# Vibration.net
KiCad netlist of a schematic drawn in Altium Designer
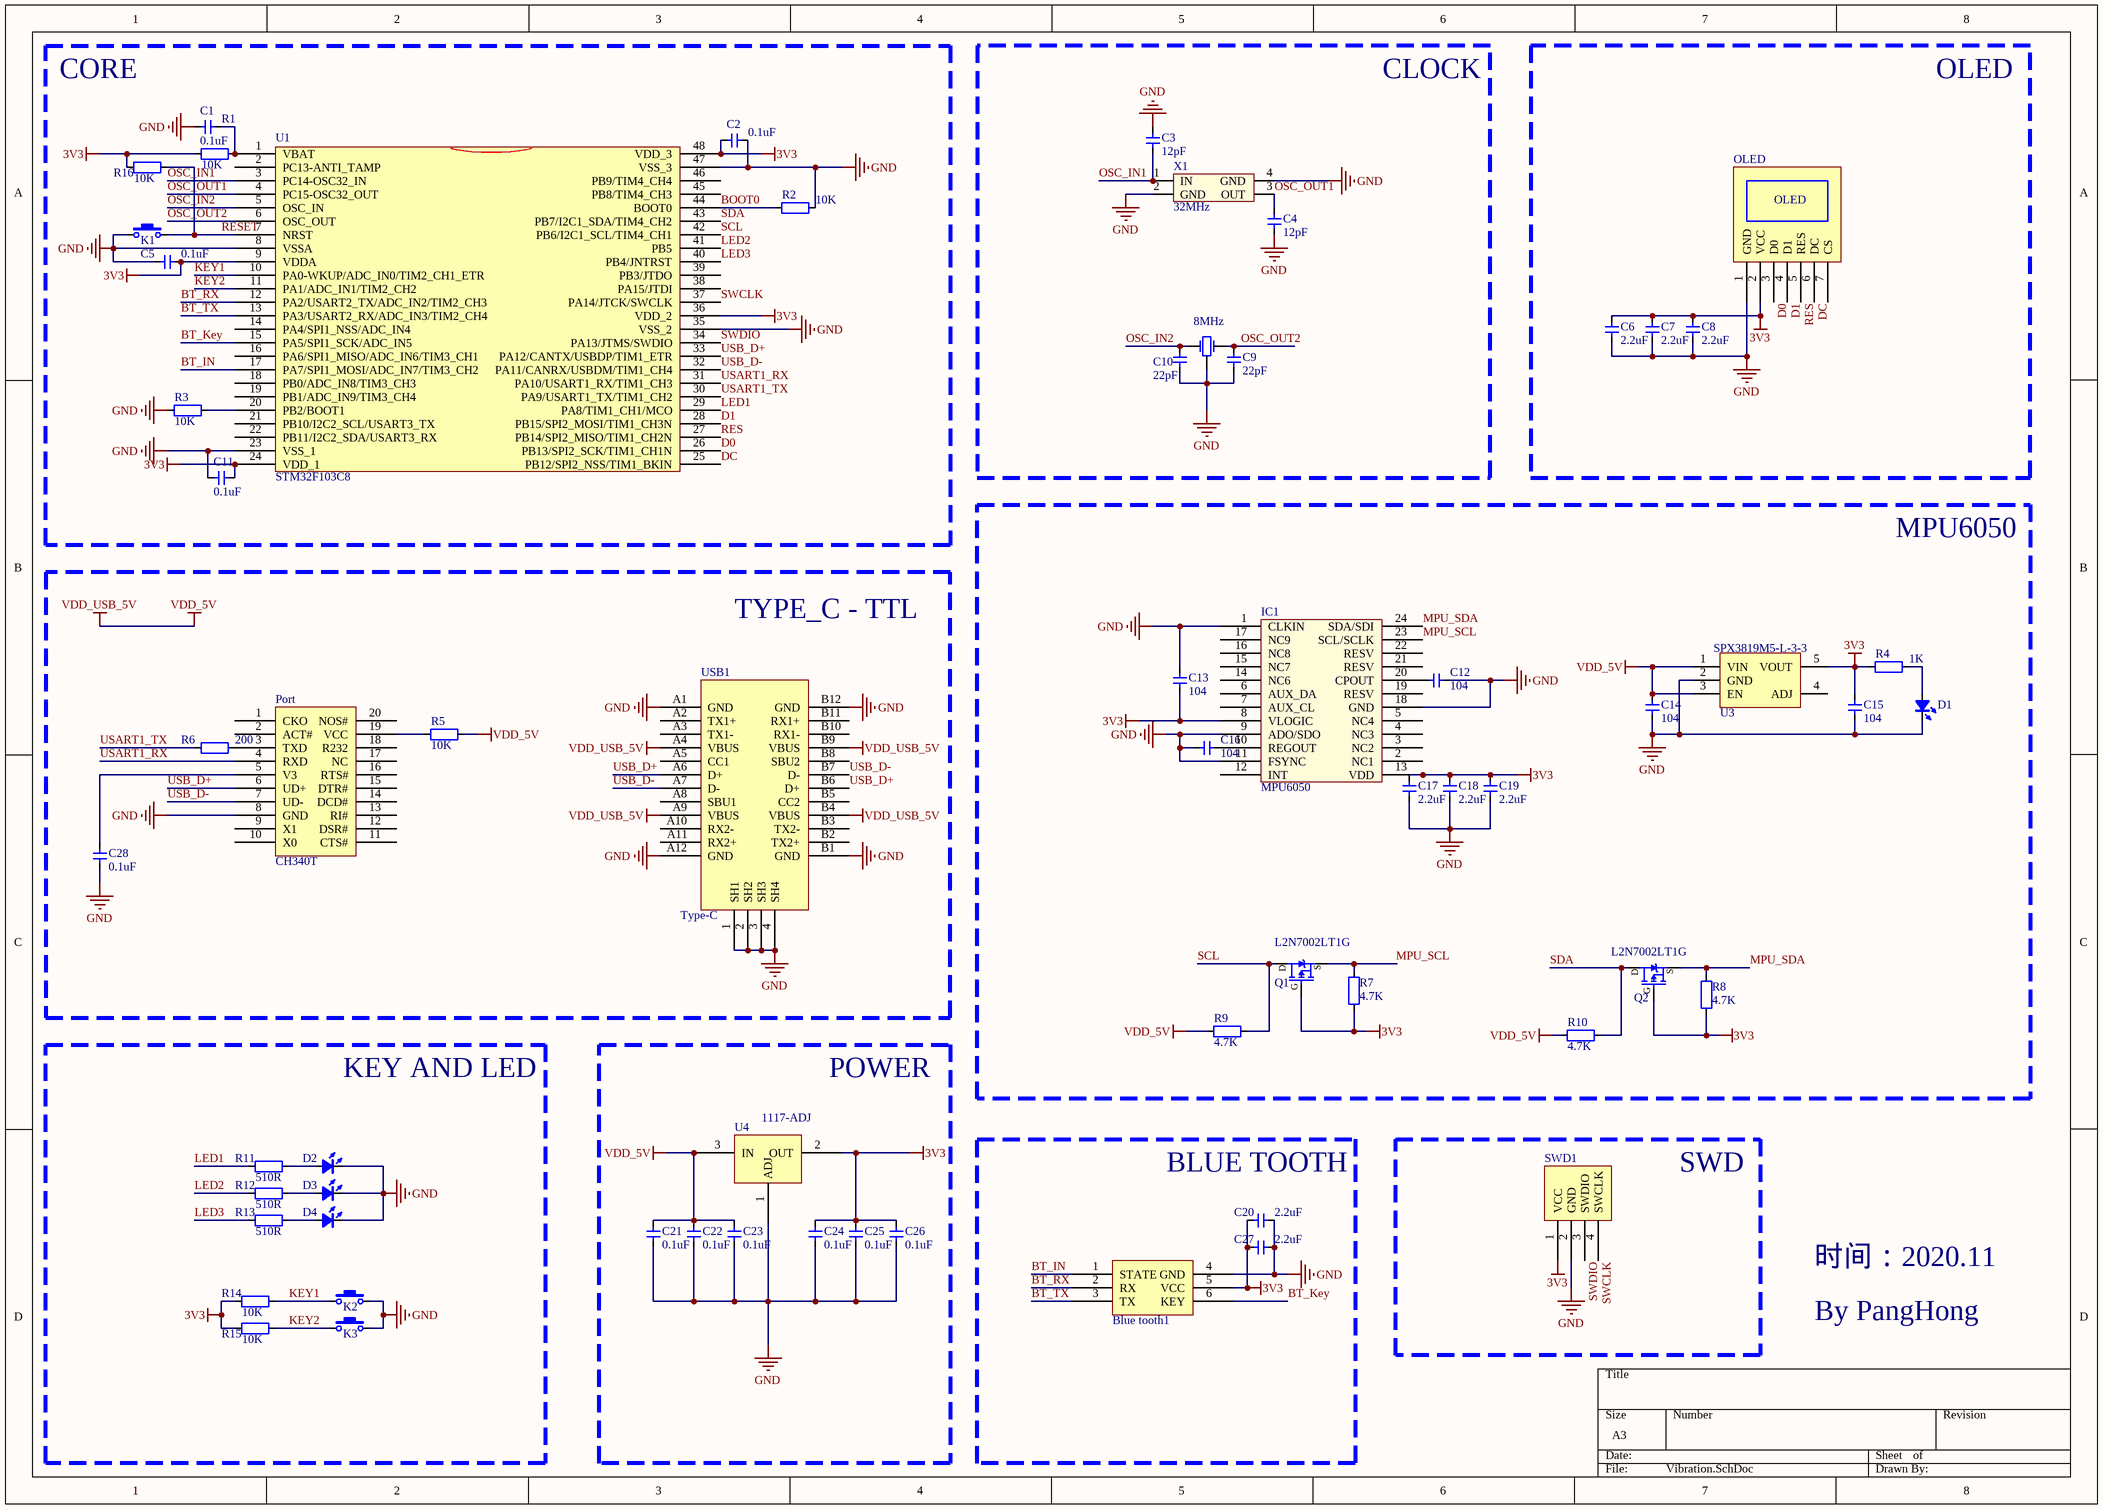
[diagram p0: Vibration.SchDoc]

(export (version "E")
  (design (tool "Eeschema 10.0.6"))
  (components
    (comp (ref "Blue tooth1")
      (value "Blue tooth")
      (footprint "蓝牙")
      (libsource (lib "Vibration") (part "Blue tooth"))
    )
    (comp (ref "C1")
      (value "0.1uF")
      (footprint "CAP_0402")
      (description "Capacitor")
      (libsource (lib "Vibration") (part "电容-0402"))
    )
    (comp (ref "C2")
      (value "0.1uF")
      (footprint "CAP_0402")
      (description "Capacitor")
      (libsource (lib "Vibration") (part "电容-0402"))
    )
    (comp (ref "C3")
      (value "12pF")
      (footprint "CAP_0402")
      (description "Capacitor")
      (libsource (lib "Vibration") (part "电容-0402"))
    )
    (comp (ref "C4")
      (value "12pF")
      (footprint "CAP_0402")
      (description "Capacitor")
      (libsource (lib "Vibration") (part "电容-0402"))
    )
    (comp (ref "C5")
      (value "0.1uF")
      (footprint "CAP_0402")
      (description "Capacitor")
      (libsource (lib "Vibration") (part "电容-0402"))
    )
    (comp (ref "C6")
      (value "2.2uF")
      (footprint "CAP_0402")
      (description "Capacitor")
      (libsource (lib "Vibration") (part "电容-0402"))
    )
    (comp (ref "C7")
      (value "2.2uF")
      (footprint "CAP_0402")
      (description "Capacitor")
      (libsource (lib "Vibration") (part "电容-0402"))
    )
    (comp (ref "C8")
      (value "2.2uF")
      (footprint "CAP_0402")
      (description "Capacitor")
      (libsource (lib "Vibration") (part "电容-0402"))
    )
    (comp (ref "C9")
      (value "22pF")
      (footprint "CAP_0402")
      (description "Capacitor")
      (libsource (lib "Vibration") (part "电容-0402"))
    )
    (comp (ref "C10")
      (value "22pF")
      (footprint "CAP_0402")
      (description "Capacitor")
      (libsource (lib "Vibration") (part "电容-0402"))
    )
    (comp (ref "C11")
      (value "0.1uF")
      (footprint "CAP_0402")
      (description "Capacitor")
      (libsource (lib "Vibration") (part "电容-0402"))
    )
    (comp (ref "C12")
      (value "104")
      (footprint "CAP_0402")
      (description "Capacitor")
      (libsource (lib "Vibration") (part "电容-0402"))
    )
    (comp (ref "C13")
      (value "104")
      (footprint "CAP_0402")
      (description "Capacitor")
      (libsource (lib "Vibration") (part "电容-0402"))
    )
    (comp (ref "C14")
      (value "104")
      (footprint "CAP_0402")
      (description "Capacitor")
      (libsource (lib "Vibration") (part "电容-0402"))
    )
    (comp (ref "C15")
      (value "104")
      (footprint "CAP_0402")
      (description "Capacitor")
      (libsource (lib "Vibration") (part "电容-0402"))
    )
    (comp (ref "C16")
      (value "104")
      (footprint "CAP_0402")
      (description "Capacitor")
      (libsource (lib "Vibration") (part "电容-0402"))
    )
    (comp (ref "C17")
      (value "2.2uF")
      (footprint "CAP_0402")
      (description "Capacitor")
      (libsource (lib "Vibration") (part "电容-0402"))
    )
    (comp (ref "C18")
      (value "2.2uF")
      (footprint "CAP_0402")
      (description "Capacitor")
      (libsource (lib "Vibration") (part "电容-0402"))
    )
    (comp (ref "C19")
      (value "2.2uF")
      (footprint "CAP_0402")
      (description "Capacitor")
      (libsource (lib "Vibration") (part "电容-0402"))
    )
    (comp (ref "C20")
      (value "2.2uF")
      (footprint "CAP_0402")
      (description "Capacitor")
      (libsource (lib "Vibration") (part "电容-0402"))
    )
    (comp (ref "C21")
      (value "0.1uF")
      (footprint "0603-CAP")
      (description "Capacitor")
      (libsource (lib "Vibration") (part "电容-0603"))
    )
    (comp (ref "C22")
      (value "0.1uF")
      (footprint "0603-CAP")
      (description "Capacitor")
      (libsource (lib "Vibration") (part "电容-0603"))
    )
    (comp (ref "C23")
      (value "0.1uF")
      (footprint "0603-CAP")
      (description "Capacitor")
      (libsource (lib "Vibration") (part "电容-0603"))
    )
    (comp (ref "C24")
      (value "0.1uF")
      (footprint "0603-CAP")
      (description "Capacitor")
      (libsource (lib "Vibration") (part "电容-0603"))
    )
    (comp (ref "C25")
      (value "0.1uF")
      (footprint "0603-CAP")
      (description "Capacitor")
      (libsource (lib "Vibration") (part "电容-0603"))
    )
    (comp (ref "C26")
      (value "0.1uF")
      (footprint "0603-CAP")
      (description "Capacitor")
      (libsource (lib "Vibration") (part "电容-0603"))
    )
    (comp (ref "C27")
      (value "2.2uF")
      (footprint "CAP_0402")
      (description "Capacitor")
      (libsource (lib "Vibration") (part "电容-0402"))
    )
    (comp (ref "C28")
      (value "0.1uF")
      (footprint "CAP_0402")
      (description "Capacitor")
      (libsource (lib "Vibration") (part "电容-0402"))
    )
    (comp (ref "D1")
      (value "color?")
      (footprint "LED_0402_BLUE")
      (description "LED")
      (libsource (lib "") (part "LED_0402_1"))
    )
    (comp (ref "D2")
      (value "color?")
      (footprint "LED_0402_BLUE")
      (description "LED")
      (libsource (lib "Vibration") (part "LED_0402"))
    )
    (comp (ref "D3")
      (value "color?")
      (footprint "LED_0402_BLUE")
      (description "LED")
      (libsource (lib "Vibration") (part "LED_0402"))
    )
    (comp (ref "D4")
      (value "color?")
      (footprint "LED_0402_BLUE")
      (description "LED")
      (libsource (lib "Vibration") (part "LED_0402"))
    )
    (comp (ref "IC1")
      (value "MPU6050")
      (footprint "QFN24 - 4*4*0.9")
      (libsource (lib "Vibration") (part "MPU6000"))
    )
    (comp (ref "K1")
      (value "TACT 2P")
      (footprint "ButtonTACT_3x4x2_180H")
      (description "Button")
      (libsource (lib "Vibration") (part "ButtonTACT_3x4x2_180"))
    )
    (comp (ref "K2")
      (value "TACT 2P")
      (footprint "ButtonTACT_3x4x2_180H")
      (description "Button")
      (libsource (lib "Vibration") (part "ButtonTACT_3x4x2_180"))
    )
    (comp (ref "K3")
      (value "TACT 2P")
      (footprint "ButtonTACT_3x4x2_180H")
      (description "Button")
      (libsource (lib "Vibration") (part "ButtonTACT_3x4x2_180"))
    )
    (comp (ref "OLED") (value "OLED") (footprint "OLED 0.96") (libsource (lib "Vibration") (part "OLED")))
    (comp (ref "Port")
      (value "CH340T")
      (footprint "SSOP-20")
      (description "Port")
      (libsource (lib "Vibration") (part "CH340T"))
    )
    (comp (ref "Q1")
      (value "L2N7002LT1G")
      (footprint "SOT23-3N")
      (description "P沟道 20V/2.8A")
      (fields (field (name "版权归属") "源创客"))
      (libsource (lib "Vibration") (part "SI2301"))
    )
    (comp (ref "Q2")
      (value "L2N7002LT1G")
      (footprint "SOT23-3N")
      (description "P沟道 20V/2.8A")
      (fields (field (name "版权归属") "源创客"))
      (libsource (lib "6.1   - 场效应管-可控硅") (part "SI2301"))
    )
    (comp (ref "R1")
      (value "10K")
      (footprint "RES_0402")
      (description "Resistor")
      (libsource (lib "") (part "电阻-0402_1"))
    )
    (comp (ref "R2")
      (value "10K")
      (footprint "RES_0402")
      (description "Resistor")
      (libsource (lib "") (part "电阻-0402_1"))
    )
    (comp (ref "R3")
      (value "10K")
      (footprint "RES_0402")
      (description "Resistor")
      (libsource (lib "") (part "电阻-0402_1"))
    )
    (comp (ref "R4")
      (value "1K")
      (footprint "RES_0402")
      (description "Resistor")
      (libsource (lib "") (part "电阻-0402_1"))
    )
    (comp (ref "R5")
      (value "10K")
      (footprint "RES_0402")
      (description "Resistor")
      (libsource (lib "") (part "电阻-0402_1"))
    )
    (comp (ref "R6")
      (value "200")
      (footprint "RES_0402")
      (description "Resistor")
      (libsource (lib "") (part "电阻-0402_1"))
    )
    (comp (ref "R7")
      (value "4.7K")
      (footprint "RES_0402")
      (description "Resistor")
      (libsource (lib "Vibration") (part "电阻-0402"))
    )
    (comp (ref "R8")
      (value "4.7K")
      (footprint "RES_0402")
      (description "Resistor")
      (libsource (lib "Vibration") (part "电阻-0402"))
    )
    (comp (ref "R9")
      (value "4.7K")
      (footprint "RES_0402")
      (description "Resistor")
      (libsource (lib "") (part "电阻-0402_2"))
    )
    (comp (ref "R10")
      (value "4.7K")
      (footprint "RES_0402")
      (description "Resistor")
      (libsource (lib "") (part "电阻-0402_2"))
    )
    (comp (ref "R11")
      (value "510R")
      (footprint "RES_0402")
      (description "Resistor")
      (libsource (lib "") (part "电阻-0402_1"))
    )
    (comp (ref "R12")
      (value "510R")
      (footprint "RES_0402")
      (description "Resistor")
      (libsource (lib "") (part "电阻-0402_1"))
    )
    (comp (ref "R13")
      (value "510R")
      (footprint "RES_0402")
      (description "Resistor")
      (libsource (lib "") (part "电阻-0402_1"))
    )
    (comp (ref "R14")
      (value "10K")
      (footprint "RES_0402")
      (description "Resistor")
      (libsource (lib "") (part "电阻-0402_1"))
    )
    (comp (ref "R15")
      (value "10K")
      (footprint "RES_0402")
      (description "Resistor")
      (libsource (lib "") (part "电阻-0402_1"))
    )
    (comp (ref "R16")
      (value "10K")
      (footprint "RES_0402")
      (description "Resistor")
      (libsource (lib "") (part "电阻-0402_2"))
    )
    (comp (ref "SWD1") (value "SWD") (footprint "SWD") (libsource (lib "Vibration") (part "SWD")))
    (comp (ref "U1")
      (value "STM32F103C8")
      (footprint "LQFP48_M")
      (libsource (lib "REMOTOR") (part "STM32F103C6"))
    )
    (comp (ref "U3")
      (value "SPX3819M5")
      (footprint "L - SOT23-5L")
      (fields (field (name "版权所有") "Ly"))
      (libsource (lib "Vibration") (part "SPX3819M5"))
    )
    (comp (ref "U4")
      (value "1117-ADJ")
      (footprint "SOT223_JX")
      (description "IC")
      (libsource (lib "Vibration") (part "AMS1117-ADJ"))
    )
    (comp (ref "USB1")
      (value "Type-C")
      (footprint "Type-C-TOP")
      (libsource (lib "Vibration") (part "USB-Type-C-TOP"))
    )
    (comp (ref "X1")
      (value "32MHz")
      (footprint "XTAL3225   无源")
      (description "无源贴片晶振")
      (libsource (lib "MiniFly ") (part "XTAL-无源贴片"))
    )
    (comp (ref "X2") (value "8MHz") (footprint "XTAL3215") (libsource (lib "MiniFly ") (part "XTAL-3215")))
  )
  (nets
    (net (code "1") (name "/BOOT0") (class "Default")
      (node (ref "R2") (pin "1") (pinfunction "1_1") (pintype "passive"))
      (node (ref "U1") (pin "44") (pinfunction "BOOT0_44") (pintype "passive"))
    )
    (net (code "2") (name "/BT_IN") (class "Default")
      (node (ref "Blue tooth1") (pin "1") (pinfunction "STATE_1") (pintype "passive"))
      (node (ref "U1") (pin "17") (pinfunction "PA7/SPI1_MOSI/ADC_IN7/TIM3_CH2_17") (pintype "passive"))
    )
    (net (code "3") (name "/BT_Key") (class "Default")
      (node (ref "Blue tooth1") (pin "6") (pinfunction "KEY_6") (pintype "passive"))
      (node (ref "U1") (pin "15") (pinfunction "PA5/SPI1_SCK/ADC_IN5_15") (pintype "passive"))
    )
    (net (code "4") (name "/BT_RX") (class "Default")
      (node (ref "Blue tooth1") (pin "2") (pinfunction "RX_2") (pintype "passive"))
      (node (ref "U1") (pin "12") (pinfunction "PA2/USART2_TX/ADC_IN2/TIM2_CH3_12") (pintype "passive"))
    )
    (net (code "5") (name "/BT_TX") (class "Default")
      (node (ref "Blue tooth1") (pin "3") (pinfunction "TX_3") (pintype "passive"))
      (node (ref "U1") (pin "13") (pinfunction "PA3/USART2_RX/ADC_IN3/TIM2_CH4_13") (pintype "passive"))
    )
    (net (code "6") (name "/D0") (class "Default")
      (node (ref "OLED") (pin "3") (pinfunction "D0_3") (pintype "passive"))
      (node (ref "U1") (pin "26") (pinfunction "PB13/SPI2_SCK/TIM1_CH1N_26") (pintype "passive"))
    )
    (net (code "7") (name "/D1") (class "Default")
      (node (ref "OLED") (pin "4") (pinfunction "D1_4") (pintype "passive"))
      (node (ref "U1") (pin "28") (pinfunction "PB15/SPI2_MOSI/TIM1_CH3N_28") (pintype "passive"))
    )
    (net (code "8") (name "/DC") (class "Default")
      (node (ref "OLED") (pin "6") (pinfunction "DC_6") (pintype "passive"))
      (node (ref "U1") (pin "25") (pinfunction "PB12/SPI2_NSS/TIM1_BKIN_25") (pintype "passive"))
    )
    (net (code "9") (name "/KEY1") (class "Default")
      (node (ref "K2") (pin "1") (pinfunction "1_1") (pintype "passive"))
      (node (ref "R14") (pin "2") (pinfunction "2_2") (pintype "passive"))
      (node (ref "U1") (pin "10") (pinfunction "PA0-WKUP/ADC_IN0/TIM2_CH1_ETR_10") (pintype "passive"))
    )
    (net (code "10") (name "/KEY2") (class "Default")
      (node (ref "K3") (pin "1") (pinfunction "1_1") (pintype "passive"))
      (node (ref "R15") (pin "2") (pinfunction "2_2") (pintype "passive"))
      (node (ref "U1") (pin "11") (pinfunction "PA1/ADC_IN1/TIM2_CH2_11") (pintype "passive"))
    )
    (net (code "11") (name "/LED1") (class "Default")
      (node (ref "R11") (pin "1") (pinfunction "1_1") (pintype "passive"))
      (node (ref "U1") (pin "29") (pinfunction "PA8/TIM1_CH1/MCO_29") (pintype "passive"))
    )
    (net (code "12") (name "/LED2") (class "Default")
      (node (ref "R12") (pin "1") (pinfunction "1_1") (pintype "passive"))
      (node (ref "U1") (pin "41") (pinfunction "PB5_41") (pintype "passive"))
    )
    (net (code "13") (name "/LED3") (class "Default")
      (node (ref "R13") (pin "1") (pinfunction "1_1") (pintype "passive"))
      (node (ref "U1") (pin "40") (pinfunction "PB4/JNTRST_40") (pintype "passive"))
    )
    (net (code "14") (name "/MPU_SCL") (class "Default")
      (node (ref "IC1") (pin "23") (pinfunction "SCL/SCLK_23") (pintype "passive"))
      (node (ref "Q1") (pin "2") (pinfunction "S_2") (pintype "passive"))
      (node (ref "R7") (pin "2") (pinfunction "2_2") (pintype "passive"))
    )
    (net (code "15") (name "/MPU_SDA") (class "Default")
      (node (ref "IC1") (pin "24") (pinfunction "SDA/SDI_24") (pintype "passive"))
      (node (ref "Q2") (pin "2") (pinfunction "S_2") (pintype "passive"))
      (node (ref "R8") (pin "2") (pinfunction "2_2") (pintype "passive"))
    )
    (net (code "16") (name "/OSC_IN1") (class "Default")
      (node (ref "C3") (pin "1") (pinfunction "1_1") (pintype "passive"))
      (node (ref "U1") (pin "3") (pinfunction "PC14-OSC32_IN_3") (pintype "passive"))
      (node (ref "X1") (pin "1") (pinfunction "IN_1") (pintype "passive"))
    )
    (net (code "17") (name "/OSC_IN2") (class "Default")
      (node (ref "C10") (pin "2") (pinfunction "2_2") (pintype "passive"))
      (node (ref "U1") (pin "5") (pinfunction "OSC_IN_5") (pintype "passive"))
      (node (ref "X2") (pin "1") (pinfunction "OSC1_1") (pintype "passive"))
    )
    (net (code "18") (name "/OSC_OUT1") (class "Default")
      (node (ref "C4") (pin "2") (pinfunction "2_2") (pintype "passive"))
      (node (ref "U1") (pin "4") (pinfunction "PC15-OSC32_OUT_4") (pintype "passive"))
      (node (ref "X1") (pin "3") (pinfunction "OUT_3") (pintype "passive"))
    )
    (net (code "19") (name "/OSC_OUT2") (class "Default")
      (node (ref "C9") (pin "2") (pinfunction "2_2") (pintype "passive"))
      (node (ref "U1") (pin "6") (pinfunction "OSC_OUT_6") (pintype "passive"))
      (node (ref "X2") (pin "3") (pinfunction "OSC2_3") (pintype "passive"))
    )
    (net (code "20") (name "/RES") (class "Default")
      (node (ref "OLED") (pin "5") (pinfunction "RES_5") (pintype "passive"))
      (node (ref "U1") (pin "27") (pinfunction "PB14/SPI2_MISO/TIM1_CH2N_27") (pintype "passive"))
    )
    (net (code "21") (name "/RESET") (class "Default")
      (node (ref "K1") (pin "2") (pinfunction "2_2") (pintype "passive"))
      (node (ref "R16") (pin "1") (pinfunction "1_1") (pintype "passive"))
      (node (ref "U1") (pin "7") (pinfunction "NRST_7") (pintype "passive"))
    )
    (net (code "22") (name "/SCL") (class "Default")
      (node (ref "Q1") (pin "3") (pinfunction "D_3") (pintype "passive"))
      (node (ref "R9") (pin "1") (pinfunction "1_1") (pintype "passive"))
      (node (ref "U1") (pin "42") (pinfunction "PB6/I2C1_SCL/TIM4_CH1_42") (pintype "passive"))
    )
    (net (code "23") (name "/SDA") (class "Default")
      (node (ref "Q2") (pin "3") (pinfunction "D_3") (pintype "passive"))
      (node (ref "R10") (pin "1") (pinfunction "1_1") (pintype "passive"))
      (node (ref "U1") (pin "43") (pinfunction "PB7/I2C1_SDA/TIM4_CH2_43") (pintype "passive"))
    )
    (net (code "24") (name "/SWCLK") (class "Default")
      (node (ref "SWD1") (pin "4") (pinfunction "SWCLK_4") (pintype "passive"))
      (node (ref "U1") (pin "37") (pinfunction "PA14/JTCK/SWCLK_37") (pintype "passive"))
    )
    (net (code "25") (name "/SWDIO") (class "Default")
      (node (ref "SWD1") (pin "3") (pinfunction "SWDIO_3") (pintype "passive"))
      (node (ref "U1") (pin "34") (pinfunction "PA13/JTMS/SWDIO_34") (pintype "passive"))
    )
    (net (code "26") (name "/USART1_RX") (class "Default")
      (node (ref "Port") (pin "4") (pinfunction "RXD_4") (pintype "passive"))
      (node (ref "U1") (pin "31") (pinfunction "PA10/USART1_RX/TIM1_CH3_31") (pintype "passive"))
    )
    (net (code "27") (name "/USART1_TX") (class "Default")
      (node (ref "R6") (pin "1") (pinfunction "1_1") (pintype "passive"))
      (node (ref "U1") (pin "30") (pinfunction "PA9/USART1_TX/TIM1_CH2_30") (pintype "passive"))
    )
    (net (code "28") (name "/USB_D+") (class "Default")
      (node (ref "Port") (pin "6") (pinfunction "UD+_6") (pintype "passive"))
      (node (ref "U1") (pin "33") (pinfunction "PA12/CANTX/USBDP/TIM1_ETR_33") (pintype "passive"))
      (node (ref "USB1") (pin "A6") (pinfunction "D+_A6") (pintype "passive"))
      (node (ref "USB1") (pin "B6") (pinfunction "D+_B6") (pintype "passive"))
    )
    (net (code "29") (name "/USB_D-") (class "Default")
      (node (ref "Port") (pin "7") (pinfunction "UD-_7") (pintype "passive"))
      (node (ref "U1") (pin "32") (pinfunction "PA11/CANRX/USBDM/TIM1_CH4_32") (pintype "passive"))
      (node (ref "USB1") (pin "A7") (pinfunction "D-_A7") (pintype "passive"))
      (node (ref "USB1") (pin "B7") (pinfunction "D-_B7") (pintype "passive"))
    )
    (net (code "30") (name "3V3") (class "Default")
      (node (ref "Blue tooth1") (pin "5") (pinfunction "VCC_5") (pintype "passive"))
      (node (ref "C11") (pin "2") (pinfunction "2_2") (pintype "passive"))
      (node (ref "C13") (pin "1") (pinfunction "1_1") (pintype "passive"))
      (node (ref "C15") (pin "1") (pinfunction "1_1") (pintype "passive"))
      (node (ref "C17") (pin "1") (pinfunction "1_1") (pintype "passive"))
      (node (ref "C18") (pin "1") (pinfunction "1_1") (pintype "passive"))
      (node (ref "C19") (pin "1") (pinfunction "1_1") (pintype "passive"))
      (node (ref "C2") (pin "1") (pinfunction "1_1") (pintype "passive"))
      (node (ref "C20") (pin "1") (pinfunction "1_1") (pintype "passive"))
      (node (ref "C24") (pin "2") (pinfunction "2_2") (pintype "passive"))
      (node (ref "C25") (pin "2") (pinfunction "2_2") (pintype "passive"))
      (node (ref "C26") (pin "2") (pinfunction "2_2") (pintype "passive"))
      (node (ref "C27") (pin "1") (pinfunction "1_1") (pintype "passive"))
      (node (ref "C5") (pin "2") (pinfunction "2_2") (pintype "passive"))
      (node (ref "C6") (pin "1") (pinfunction "1_1") (pintype "passive"))
      (node (ref "C7") (pin "1") (pinfunction "1_1") (pintype "passive"))
      (node (ref "C8") (pin "1") (pinfunction "1_1") (pintype "passive"))
      (node (ref "IC1") (pin "13") (pinfunction "VDD_13") (pintype "passive"))
      (node (ref "IC1") (pin "8") (pinfunction "VLOGIC_8") (pintype "passive"))
      (node (ref "OLED") (pin "2") (pinfunction "VCC_2") (pintype "passive"))
      (node (ref "Q1") (pin "1") (pinfunction "G_1") (pintype "passive"))
      (node (ref "Q2") (pin "1") (pinfunction "G_1") (pintype "passive"))
      (node (ref "R1") (pin "1") (pinfunction "1_1") (pintype "passive"))
      (node (ref "R14") (pin "1") (pinfunction "1_1") (pintype "passive"))
      (node (ref "R15") (pin "1") (pinfunction "1_1") (pintype "passive"))
      (node (ref "R16") (pin "2") (pinfunction "2_2") (pintype "passive"))
      (node (ref "R4") (pin "1") (pinfunction "1_1") (pintype "passive"))
      (node (ref "R7") (pin "1") (pinfunction "1_1") (pintype "passive"))
      (node (ref "R8") (pin "1") (pinfunction "1_1") (pintype "passive"))
      (node (ref "SWD1") (pin "1") (pinfunction "VCC_1") (pintype "passive"))
      (node (ref "U1") (pin "24") (pinfunction "VDD_1_24") (pintype "passive"))
      (node (ref "U1") (pin "36") (pinfunction "VDD_2_36") (pintype "passive"))
      (node (ref "U1") (pin "48") (pinfunction "VDD_3_48") (pintype "passive"))
      (node (ref "U1") (pin "9") (pinfunction "VDDA_9") (pintype "passive"))
      (node (ref "U3") (pin "5") (pinfunction "VOUT_5") (pintype "passive"))
      (node (ref "U4") (pin "2") (pinfunction "OUT_2") (pintype "passive"))
    )
    (net (code "31") (name "GND") (class "Default")
      (node (ref "Blue tooth1") (pin "4") (pinfunction "GND_4") (pintype "passive"))
      (node (ref "C1") (pin "1") (pinfunction "1_1") (pintype "passive"))
      (node (ref "C10") (pin "1") (pinfunction "1_1") (pintype "passive"))
      (node (ref "C11") (pin "1") (pinfunction "1_1") (pintype "passive"))
      (node (ref "C12") (pin "1") (pinfunction "1_1") (pintype "passive"))
      (node (ref "C13") (pin "2") (pinfunction "2_2") (pintype "passive"))
      (node (ref "C14") (pin "2") (pinfunction "2_2") (pintype "passive"))
      (node (ref "C15") (pin "2") (pinfunction "2_2") (pintype "passive"))
      (node (ref "C16") (pin "2") (pinfunction "2_2") (pintype "passive"))
      (node (ref "C17") (pin "2") (pinfunction "2_2") (pintype "passive"))
      (node (ref "C18") (pin "2") (pinfunction "2_2") (pintype "passive"))
      (node (ref "C19") (pin "2") (pinfunction "2_2") (pintype "passive"))
      (node (ref "C2") (pin "2") (pinfunction "2_2") (pintype "passive"))
      (node (ref "C20") (pin "2") (pinfunction "2_2") (pintype "passive"))
      (node (ref "C21") (pin "1") (pinfunction "1_1") (pintype "passive"))
      (node (ref "C22") (pin "1") (pinfunction "1_1") (pintype "passive"))
      (node (ref "C23") (pin "1") (pinfunction "1_1") (pintype "passive"))
      (node (ref "C24") (pin "1") (pinfunction "1_1") (pintype "passive"))
      (node (ref "C25") (pin "1") (pinfunction "1_1") (pintype "passive"))
      (node (ref "C26") (pin "1") (pinfunction "1_1") (pintype "passive"))
      (node (ref "C27") (pin "2") (pinfunction "2_2") (pintype "passive"))
      (node (ref "C28") (pin "1") (pinfunction "1_1") (pintype "passive"))
      (node (ref "C3") (pin "2") (pinfunction "2_2") (pintype "passive"))
      (node (ref "C4") (pin "1") (pinfunction "1_1") (pintype "passive"))
      (node (ref "C5") (pin "1") (pinfunction "1_1") (pintype "passive"))
      (node (ref "C6") (pin "2") (pinfunction "2_2") (pintype "passive"))
      (node (ref "C7") (pin "2") (pinfunction "2_2") (pintype "passive"))
      (node (ref "C8") (pin "2") (pinfunction "2_2") (pintype "passive"))
      (node (ref "C9") (pin "1") (pinfunction "1_1") (pintype "passive"))
      (node (ref "D1") (pin "2") (pinfunction "K_2") (pintype "passive"))
      (node (ref "D2") (pin "2") (pinfunction "K_2") (pintype "passive"))
      (node (ref "D3") (pin "2") (pinfunction "K_2") (pintype "passive"))
      (node (ref "D4") (pin "2") (pinfunction "K_2") (pintype "passive"))
      (node (ref "IC1") (pin "1") (pinfunction "CLKIN_1") (pintype "passive"))
      (node (ref "IC1") (pin "11") (pinfunction "FSYNC_11") (pintype "passive"))
      (node (ref "IC1") (pin "18") (pinfunction "GND_18") (pintype "passive"))
      (node (ref "IC1") (pin "9") (pinfunction "ADO/SDO_9") (pintype "passive"))
      (node (ref "K1") (pin "1") (pinfunction "1_1") (pintype "passive"))
      (node (ref "K2") (pin "2") (pinfunction "2_2") (pintype "passive"))
      (node (ref "K3") (pin "2") (pinfunction "2_2") (pintype "passive"))
      (node (ref "OLED") (pin "1") (pinfunction "GND_1") (pintype "passive"))
      (node (ref "Port") (pin "8") (pinfunction "GND_8") (pintype "passive"))
      (node (ref "R2") (pin "2") (pinfunction "2_2") (pintype "passive"))
      (node (ref "R3") (pin "1") (pinfunction "1_1") (pintype "passive"))
      (node (ref "SWD1") (pin "2") (pinfunction "GND_2") (pintype "passive"))
      (node (ref "U1") (pin "23") (pinfunction "VSS_1_23") (pintype "passive"))
      (node (ref "U1") (pin "35") (pinfunction "VSS_2_35") (pintype "passive"))
      (node (ref "U1") (pin "47") (pinfunction "VSS_3_47") (pintype "passive"))
      (node (ref "U1") (pin "8") (pinfunction "VSSA_8") (pintype "passive"))
      (node (ref "U3") (pin "2") (pinfunction "GND_2") (pintype "passive"))
      (node (ref "U4") (pin "1") (pinfunction "ADJ_1") (pintype "passive"))
      (node (ref "USB1") (pin "1") (pinfunction "SH1_1") (pintype "passive"))
      (node (ref "USB1") (pin "2") (pinfunction "SH2_2") (pintype "passive"))
      (node (ref "USB1") (pin "3") (pinfunction "SH3_3") (pintype "passive"))
      (node (ref "USB1") (pin "4") (pinfunction "SH4_4") (pintype "passive"))
      (node (ref "USB1") (pin "A1") (pinfunction "GND_A1") (pintype "passive"))
      (node (ref "USB1") (pin "A12") (pinfunction "GND_A12") (pintype "passive"))
      (node (ref "USB1") (pin "B1") (pinfunction "GND_B1") (pintype "passive"))
      (node (ref "USB1") (pin "B12") (pinfunction "GND_B12") (pintype "passive"))
      (node (ref "X1") (pin "2") (pinfunction "GND_2") (pintype "passive"))
      (node (ref "X1") (pin "4") (pinfunction "GND_4") (pintype "passive"))
      (node (ref "X2") (pin "2") (pinfunction "GND_2") (pintype "passive"))
    )
    (net (code "32") (name "Net-(D1-A)") (class "Default")
      (node (ref "D1") (pin "1") (pinfunction "A_1") (pintype "passive"))
      (node (ref "R4") (pin "2") (pinfunction "2_2") (pintype "passive"))
    )
    (net (code "33") (name "Net-(D2-A)") (class "Default")
      (node (ref "D2") (pin "1") (pinfunction "A_1") (pintype "passive"))
      (node (ref "R11") (pin "2") (pinfunction "2_2") (pintype "passive"))
    )
    (net (code "34") (name "Net-(D3-A)") (class "Default")
      (node (ref "D3") (pin "1") (pinfunction "A_1") (pintype "passive"))
      (node (ref "R12") (pin "2") (pinfunction "2_2") (pintype "passive"))
    )
    (net (code "35") (name "Net-(D4-A)") (class "Default")
      (node (ref "D4") (pin "1") (pinfunction "A_1") (pintype "passive"))
      (node (ref "R13") (pin "2") (pinfunction "2_2") (pintype "passive"))
    )
    (net (code "36") (name "Net-(IC1-CPOUT)") (class "Default")
      (node (ref "C12") (pin "2") (pinfunction "2_2") (pintype "passive"))
      (node (ref "IC1") (pin "20") (pinfunction "CPOUT_20") (pintype "passive"))
    )
    (net (code "37") (name "Net-(IC1-REGOUT)") (class "Default")
      (node (ref "C16") (pin "1") (pinfunction "1_1") (pintype "passive"))
      (node (ref "IC1") (pin "10") (pinfunction "REGOUT_10") (pintype "passive"))
    )
    (net (code "38") (name "Net-(Port-TXD)") (class "Default")
      (node (ref "Port") (pin "3") (pinfunction "TXD_3") (pintype "passive"))
      (node (ref "R6") (pin "2") (pinfunction "2_2") (pintype "passive"))
    )
    (net (code "39") (name "Net-(Port-V3)") (class "Default")
      (node (ref "C28") (pin "2") (pinfunction "2_2") (pintype "passive"))
      (node (ref "Port") (pin "5") (pinfunction "V3_5") (pintype "passive"))
    )
    (net (code "40") (name "Net-(Port-VCC)") (class "Default")
      (node (ref "Port") (pin "19") (pinfunction "VCC_19") (pintype "passive"))
      (node (ref "R5") (pin "1") (pinfunction "1_1") (pintype "passive"))
    )
    (net (code "41") (name "Net-(U1-PB2{slash}BOOT1)") (class "Default")
      (node (ref "R3") (pin "2") (pinfunction "2_2") (pintype "passive"))
      (node (ref "U1") (pin "20") (pinfunction "PB2/BOOT1_20") (pintype "passive"))
    )
    (net (code "42") (name "Net-(U1-VBAT)") (class "Default")
      (node (ref "C1") (pin "2") (pinfunction "2_2") (pintype "passive"))
      (node (ref "R1") (pin "2") (pinfunction "2_2") (pintype "passive"))
      (node (ref "U1") (pin "1") (pinfunction "VBAT_1") (pintype "passive"))
    )
    (net (code "43") (name "VDD_5V") (class "Default")
      (node (ref "C14") (pin "1") (pinfunction "1_1") (pintype "passive"))
      (node (ref "C21") (pin "2") (pinfunction "2_2") (pintype "passive"))
      (node (ref "C22") (pin "2") (pinfunction "2_2") (pintype "passive"))
      (node (ref "C23") (pin "2") (pinfunction "2_2") (pintype "passive"))
      (node (ref "R10") (pin "2") (pinfunction "2_2") (pintype "passive"))
      (node (ref "R5") (pin "2") (pinfunction "2_2") (pintype "passive"))
      (node (ref "R9") (pin "2") (pinfunction "2_2") (pintype "passive"))
      (node (ref "U3") (pin "1") (pinfunction "VIN_1") (pintype "passive"))
      (node (ref "U3") (pin "3") (pinfunction "EN_3") (pintype "passive"))
      (node (ref "U4") (pin "3") (pinfunction "IN_3") (pintype "passive"))
      (node (ref "USB1") (pin "A4") (pinfunction "VBUS_A4") (pintype "passive"))
      (node (ref "USB1") (pin "A9") (pinfunction "VBUS_A9") (pintype "passive"))
      (node (ref "USB1") (pin "B4") (pinfunction "VBUS_B4") (pintype "passive"))
      (node (ref "USB1") (pin "B9") (pinfunction "VBUS_B9") (pintype "passive"))
    )
    (net (code "44") (name "unconnected-(IC1-AUX_CL-Pad7)") (class "Default")
      (node (ref "IC1") (pin "7") (pinfunction "AUX_CL_7") (pintype "passive"))
    )
    (net (code "45") (name "unconnected-(IC1-AUX_DA-Pad6)") (class "Default")
      (node (ref "IC1") (pin "6") (pinfunction "AUX_DA_6") (pintype "passive"))
    )
    (net (code "46") (name "unconnected-(IC1-INT-Pad12)") (class "Default")
      (node (ref "IC1") (pin "12") (pinfunction "INT_12") (pintype "passive"))
    )
    (net (code "47") (name "unconnected-(IC1-NC1-Pad2)") (class "Default")
      (node (ref "IC1") (pin "2") (pinfunction "NC1_2") (pintype "passive"))
    )
    (net (code "48") (name "unconnected-(IC1-NC2-Pad3)") (class "Default")
      (node (ref "IC1") (pin "3") (pinfunction "NC2_3") (pintype "passive"))
    )
    (net (code "49") (name "unconnected-(IC1-NC3-Pad4)") (class "Default")
      (node (ref "IC1") (pin "4") (pinfunction "NC3_4") (pintype "passive"))
    )
    (net (code "50") (name "unconnected-(IC1-NC4-Pad5)") (class "Default")
      (node (ref "IC1") (pin "5") (pinfunction "NC4_5") (pintype "passive"))
    )
    (net (code "51") (name "unconnected-(IC1-NC6-Pad14)") (class "Default")
      (node (ref "IC1") (pin "14") (pinfunction "NC6_14") (pintype "passive"))
    )
    (net (code "52") (name "unconnected-(IC1-NC7-Pad15)") (class "Default")
      (node (ref "IC1") (pin "15") (pinfunction "NC7_15") (pintype "passive"))
    )
    (net (code "53") (name "unconnected-(IC1-NC8-Pad16)") (class "Default")
      (node (ref "IC1") (pin "16") (pinfunction "NC8_16") (pintype "passive"))
    )
    (net (code "54") (name "unconnected-(IC1-NC9-Pad17)") (class "Default")
      (node (ref "IC1") (pin "17") (pinfunction "NC9_17") (pintype "passive"))
    )
    (net (code "55") (name "unconnected-(IC1-RESV-Pad19)") (class "Default")
      (node (ref "IC1") (pin "19") (pinfunction "RESV_19") (pintype "passive"))
    )
    (net (code "56") (name "unconnected-(IC1-RESV-Pad21)") (class "Default")
      (node (ref "IC1") (pin "21") (pinfunction "RESV_21") (pintype "passive"))
    )
    (net (code "57") (name "unconnected-(IC1-RESV-Pad22)") (class "Default")
      (node (ref "IC1") (pin "22") (pinfunction "RESV_22") (pintype "passive"))
    )
    (net (code "58") (name "unconnected-(OLED-CS-Pad7)") (class "Default")
      (node (ref "OLED") (pin "7") (pinfunction "CS_7") (pintype "passive"))
    )
    (net (code "59") (name "unconnected-(Port-ACT#-Pad2)") (class "Default")
      (node (ref "Port") (pin "2") (pinfunction "ACT#_2") (pintype "passive"))
    )
    (net (code "60") (name "unconnected-(Port-CKO-Pad1)") (class "Default")
      (node (ref "Port") (pin "1") (pinfunction "CKO_1") (pintype "passive"))
    )
    (net (code "61") (name "unconnected-(Port-CTS#-Pad11)") (class "Default")
      (node (ref "Port") (pin "11") (pinfunction "CTS#_11") (pintype "passive"))
    )
    (net (code "62") (name "unconnected-(Port-DCD#-Pad14)") (class "Default")
      (node (ref "Port") (pin "14") (pinfunction "DCD#_14") (pintype "passive"))
    )
    (net (code "63") (name "unconnected-(Port-DSR#-Pad12)") (class "Default")
      (node (ref "Port") (pin "12") (pinfunction "DSR#_12") (pintype "passive"))
    )
    (net (code "64") (name "unconnected-(Port-DTR#-Pad15)") (class "Default")
      (node (ref "Port") (pin "15") (pinfunction "DTR#_15") (pintype "passive"))
    )
    (net (code "65") (name "unconnected-(Port-NC-Pad17)") (class "Default")
      (node (ref "Port") (pin "17") (pinfunction "NC_17") (pintype "passive"))
    )
    (net (code "66") (name "unconnected-(Port-NOS#-Pad20)") (class "Default")
      (node (ref "Port") (pin "20") (pinfunction "NOS#_20") (pintype "passive"))
    )
    (net (code "67") (name "unconnected-(Port-R232-Pad18)") (class "Default")
      (node (ref "Port") (pin "18") (pinfunction "R232_18") (pintype "passive"))
    )
    (net (code "68") (name "unconnected-(Port-RI#-Pad13)") (class "Default")
      (node (ref "Port") (pin "13") (pinfunction "RI#_13") (pintype "passive"))
    )
    (net (code "69") (name "unconnected-(Port-RTS#-Pad16)") (class "Default")
      (node (ref "Port") (pin "16") (pinfunction "RTS#_16") (pintype "passive"))
    )
    (net (code "70") (name "unconnected-(Port-X0-Pad10)") (class "Default")
      (node (ref "Port") (pin "10") (pinfunction "X0_10") (pintype "passive"))
    )
    (net (code "71") (name "unconnected-(Port-X1-Pad9)") (class "Default")
      (node (ref "Port") (pin "9") (pinfunction "X1_9") (pintype "passive"))
    )
    (net (code "72") (name "unconnected-(U1-PA4{slash}SPI1_NSS{slash}ADC_IN4-Pad14)") (class "Default")
      (node (ref "U1") (pin "14") (pinfunction "PA4/SPI1_NSS/ADC_IN4_14") (pintype "passive"))
    )
    (net (code "73") (name "unconnected-(U1-PA6{slash}SPI1_MISO{slash}ADC_IN6{slash}TIM3_CH1-Pad16)") (class "Default")
      (node (ref "U1") (pin "16") (pinfunction "PA6/SPI1_MISO/ADC_IN6/TIM3_CH1_16") (pintype "passive"))
    )
    (net (code "74") (name "unconnected-(U1-PA15{slash}JTDI-Pad38)") (class "Default")
      (node (ref "U1") (pin "38") (pinfunction "PA15/JTDI_38") (pintype "passive"))
    )
    (net (code "75") (name "unconnected-(U1-PB0{slash}ADC_IN8{slash}TIM3_CH3-Pad18)") (class "Default")
      (node (ref "U1") (pin "18") (pinfunction "PB0/ADC_IN8/TIM3_CH3_18") (pintype "passive"))
    )
    (net (code "76") (name "unconnected-(U1-PB1{slash}ADC_IN9{slash}TIM3_CH4-Pad19)") (class "Default")
      (node (ref "U1") (pin "19") (pinfunction "PB1/ADC_IN9/TIM3_CH4_19") (pintype "passive"))
    )
    (net (code "77") (name "unconnected-(U1-PB3{slash}JTDO-Pad39)") (class "Default")
      (node (ref "U1") (pin "39") (pinfunction "PB3/JTDO_39") (pintype "passive"))
    )
    (net (code "78") (name "unconnected-(U1-PB8{slash}TIM4_CH3-Pad45)") (class "Default")
      (node (ref "U1") (pin "45") (pinfunction "PB8/TIM4_CH3_45") (pintype "passive"))
    )
    (net (code "79") (name "unconnected-(U1-PB9{slash}TIM4_CH4-Pad46)") (class "Default")
      (node (ref "U1") (pin "46") (pinfunction "PB9/TIM4_CH4_46") (pintype "passive"))
    )
    (net (code "80") (name "unconnected-(U1-PB10{slash}I2C2_SCL{slash}USART3_TX-Pad21)") (class "Default")
      (node (ref "U1") (pin "21") (pinfunction "PB10/I2C2_SCL/USART3_TX_21") (pintype "passive"))
    )
    (net (code "81") (name "unconnected-(U1-PB11{slash}I2C2_SDA{slash}USART3_RX-Pad22)") (class "Default")
      (node (ref "U1") (pin "22") (pinfunction "PB11/I2C2_SDA/USART3_RX_22") (pintype "passive"))
    )
    (net (code "82") (name "unconnected-(U1-PC13-ANTI_TAMP-Pad2)") (class "Default")
      (node (ref "U1") (pin "2") (pinfunction "PC13-ANTI_TAMP_2") (pintype "passive"))
    )
    (net (code "83") (name "unconnected-(U3-ADJ-Pad4)") (class "Default")
      (node (ref "U3") (pin "4") (pinfunction "ADJ_4") (pintype "passive"))
    )
    (net (code "84") (name "unconnected-(USB1-CC1-PadA5)") (class "Default")
      (node (ref "USB1") (pin "A5") (pinfunction "CC1_A5") (pintype "passive"))
    )
    (net (code "85") (name "unconnected-(USB1-CC2-PadB5)") (class "Default")
      (node (ref "USB1") (pin "B5") (pinfunction "CC2_B5") (pintype "passive"))
    )
    (net (code "86") (name "unconnected-(USB1-RX1+-PadB11)") (class "Default")
      (node (ref "USB1") (pin "B11") (pinfunction "RX1+_B11") (pintype "passive"))
    )
    (net (code "87") (name "unconnected-(USB1-RX1--PadB10)") (class "Default")
      (node (ref "USB1") (pin "B10") (pinfunction "RX1-_B10") (pintype "passive"))
    )
    (net (code "88") (name "unconnected-(USB1-RX2+-PadA11)") (class "Default")
      (node (ref "USB1") (pin "A11") (pinfunction "RX2+_A11") (pintype "passive"))
    )
    (net (code "89") (name "unconnected-(USB1-RX2--PadA10)") (class "Default")
      (node (ref "USB1") (pin "A10") (pinfunction "RX2-_A10") (pintype "passive"))
    )
    (net (code "90") (name "unconnected-(USB1-SBU1-PadA8)") (class "Default")
      (node (ref "USB1") (pin "A8") (pinfunction "SBU1_A8") (pintype "passive"))
    )
    (net (code "91") (name "unconnected-(USB1-SBU2-PadB8)") (class "Default")
      (node (ref "USB1") (pin "B8") (pinfunction "SBU2_B8") (pintype "passive"))
    )
    (net (code "92") (name "unconnected-(USB1-TX1+-PadA2)") (class "Default")
      (node (ref "USB1") (pin "A2") (pinfunction "TX1+_A2") (pintype "passive"))
    )
    (net (code "93") (name "unconnected-(USB1-TX1--PadA3)") (class "Default")
      (node (ref "USB1") (pin "A3") (pinfunction "TX1-_A3") (pintype "passive"))
    )
    (net (code "94") (name "unconnected-(USB1-TX2+-PadB2)") (class "Default")
      (node (ref "USB1") (pin "B2") (pinfunction "TX2+_B2") (pintype "passive"))
    )
    (net (code "95") (name "unconnected-(USB1-TX2--PadB3)") (class "Default")
      (node (ref "USB1") (pin "B3") (pinfunction "TX2-_B3") (pintype "passive"))
    )
  )
)
